# usb_breakout.net
KiCad netlist of a schematic drawn in EAGLE
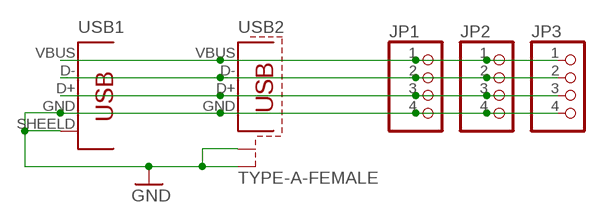
[diagram p0: schematic, sheet 1]

(export (version "E")
  (design (tool "Eeschema 10.0.6"))
  (components
    (comp (ref "JP1")
      (value "PINHD-1X4")
      (footprint "eagle-import:1X04")
      (libsource (lib "eagle-import") (part "PINHD-1X4"))
    )
    (comp (ref "JP2")
      (value "PINHD-1X4")
      (footprint "eagle-import:1X04")
      (libsource (lib "eagle-import") (part "PINHD-1X4"))
    )
    (comp (ref "JP3")
      (value "PINHD-1X4")
      (footprint "eagle-import:1X04")
      (libsource (lib "eagle-import") (part "PINHD-1X4"))
    )
    (comp (ref "USB1")
      (value "TYPE-A-MALE-SHILED")
      (footprint "eagle-import:TYPE-A-MALE")
      (libsource (lib "eagle-import") (part "TYPE-A-MALE-SHILED"))
    )
    (comp (ref "USB2")
      (value "TYPE-A-FEMALE")
      (footprint "eagle-import:TYPE-A-FEMALE")
      (libsource (lib "eagle-import") (part "TYPE-A-FEMALE"))
    )
  )
  (nets
    (net (code "1") (name "GND") (class "Default")
      (node (ref "JP1") (pin "4") (pinfunction "4_4") (pintype "passive"))
      (node (ref "JP2") (pin "4") (pinfunction "4_4") (pintype "passive"))
      (node (ref "JP3") (pin "4") (pinfunction "4_4") (pintype "passive"))
      (node (ref "USB1") (pin "GND") (pinfunction "4_GND") (pintype "power_in"))
      (node (ref "USB1") (pin "SHEELD") (pinfunction "5_SHEELD") (pintype "passive"))
      (node (ref "USB2") (pin "GND") (pinfunction "GND_GND") (pintype "passive"))
      (node (ref "USB2") (pin "S1") (pinfunction "S1_S1") (pintype "passive"))
      (node (ref "USB2") (pin "S2") (pinfunction "S2_S2") (pintype "passive"))
    )
    (net (code "2") (name "Net-(USB1-1)") (class "Default")
      (node (ref "JP1") (pin "1") (pinfunction "1_1") (pintype "passive"))
      (node (ref "JP2") (pin "1") (pinfunction "1_1") (pintype "passive"))
      (node (ref "JP3") (pin "1") (pinfunction "1_1") (pintype "passive"))
      (node (ref "USB1") (pin "VBUS") (pinfunction "1_VBUS") (pintype "power_in"))
      (node (ref "USB2") (pin "VBUS") (pinfunction "VCC_VBUS") (pintype "passive"))
    )
    (net (code "3") (name "Net-(USB1-2)") (class "Default")
      (node (ref "JP1") (pin "2") (pinfunction "2_2") (pintype "passive"))
      (node (ref "JP2") (pin "2") (pinfunction "2_2") (pintype "passive"))
      (node (ref "JP3") (pin "2") (pinfunction "2_2") (pintype "passive"))
      (node (ref "USB1") (pin "D-") (pinfunction "2_D-") (pintype "passive"))
      (node (ref "USB2") (pin "D-") (pinfunction "D-_D-") (pintype "passive"))
    )
    (net (code "4") (name "Net-(USB1-3)") (class "Default")
      (node (ref "JP1") (pin "3") (pinfunction "3_3") (pintype "passive"))
      (node (ref "JP2") (pin "3") (pinfunction "3_3") (pintype "passive"))
      (node (ref "JP3") (pin "3") (pinfunction "3_3") (pintype "passive"))
      (node (ref "USB1") (pin "D+") (pinfunction "3_D+") (pintype "passive"))
      (node (ref "USB2") (pin "D+") (pinfunction "D+_D+") (pintype "passive"))
    )
  )
)
